# pcb_v3.net
KiCad netlist of a schematic drawn in EAGLE
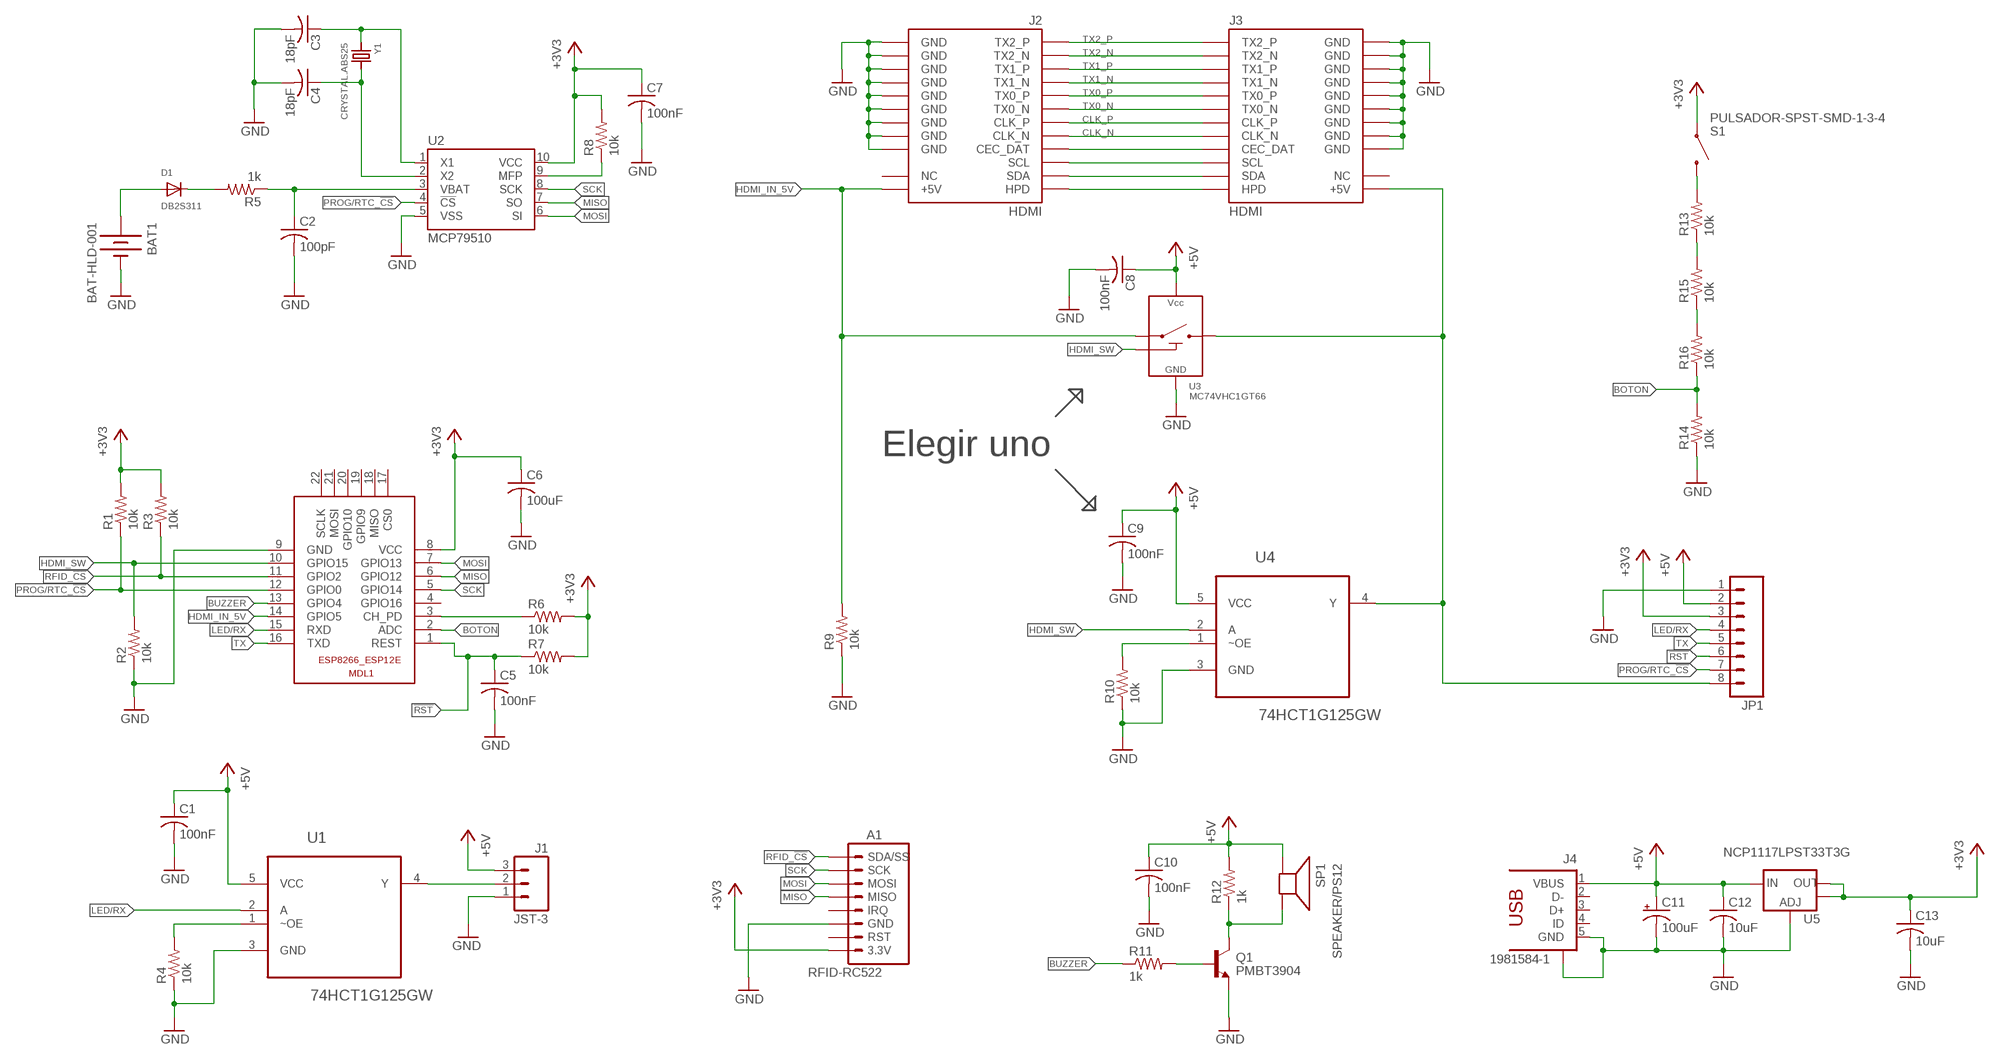
[diagram p0: schematic, sheet 1]

(export (version "E")
  (design (tool "Eeschema 10.0.6"))
  (components
    (comp (ref "A1")
      (value "RFID-RC522")
      (footprint "eagle-import:RFID-RC522")
      (libsource (lib "eagle-import") (part "RFID-RC522"))
    )
    (comp (ref "BAT1")
      (value "BAT-HLD-001")
      (footprint "eagle-import:BATTCON_20MM")
      (libsource (lib "eagle-import") (part "LINX-BAT-HLD-00120SMD"))
    )
    (comp (ref "C1")
      (value "100nF")
      (footprint "eagle-import:C0805")
      (libsource (lib "eagle-import") (part "C-USC0805"))
    )
    (comp (ref "C2")
      (value "100pF")
      (footprint "eagle-import:C0805")
      (libsource (lib "eagle-import") (part "C-USC0805"))
    )
    (comp (ref "C3")
      (value "18pF")
      (footprint "eagle-import:C0805")
      (libsource (lib "eagle-import") (part "C-USC0805"))
    )
    (comp (ref "C4")
      (value "18pF")
      (footprint "eagle-import:C0805")
      (libsource (lib "eagle-import") (part "C-USC0805"))
    )
    (comp (ref "C5")
      (value "100nF")
      (footprint "eagle-import:C0805")
      (libsource (lib "eagle-import") (part "C-USC0805"))
    )
    (comp (ref "C6")
      (value "100uF")
      (footprint "eagle-import:C1206")
      (libsource (lib "eagle-import") (part "C-USC1206"))
    )
    (comp (ref "C7")
      (value "100nF")
      (footprint "eagle-import:C0805")
      (libsource (lib "eagle-import") (part "C-USC0805"))
    )
    (comp (ref "C8")
      (value "100nF")
      (footprint "eagle-import:C0805")
      (libsource (lib "eagle-import") (part "C-USC0805"))
    )
    (comp (ref "C9")
      (value "100nF")
      (footprint "eagle-import:C0805")
      (libsource (lib "eagle-import") (part "C-USC0805"))
    )
    (comp (ref "C10")
      (value "100nF")
      (footprint "eagle-import:C0805")
      (libsource (lib "eagle-import") (part "C-USC0805"))
    )
    (comp (ref "C11")
      (value "100uF")
      (footprint "eagle-import:UD-6,3X5,8_NICHICON_LPADS")
      (libsource (lib "eagle-import") (part "CPOL-US"))
    )
    (comp (ref "C12")
      (value "10uF")
      (footprint "eagle-import:C0805")
      (libsource (lib "eagle-import") (part "C-USC0805"))
    )
    (comp (ref "C13")
      (value "10uF")
      (footprint "eagle-import:C0805")
      (libsource (lib "eagle-import") (part "C-USC0805"))
    )
    (comp (ref "D1")
      (value "DB2S311")
      (footprint "eagle-import:SOD-523")
      (libsource (lib "eagle-import") (part "DIODESOD-523"))
    )
    (comp (ref "J1")
      (value "JST-3")
      (footprint "eagle-import:B3B-PH-SM4-TB")
      (libsource (lib "eagle-import") (part "JST-3"))
    )
    (comp (ref "J2")
      (value "HDMI")
      (footprint "eagle-import:0471511071")
      (libsource (lib "eagle-import") (part "HDMI"))
    )
    (comp (ref "J3")
      (value "HDMI")
      (footprint "eagle-import:0471511071")
      (libsource (lib "eagle-import") (part "HDMI"))
    )
    (comp (ref "J4")
      (value "1981584-1")
      (footprint "eagle-import:1981584-1")
      (libsource (lib "eagle-import") (part "1981584-1"))
    )
    (comp (ref "JP1")
      (value "M081X08")
      (footprint "eagle-import:1X08")
      (libsource (lib "eagle-import") (part "M081X08"))
    )
    (comp (ref "MDL1")
      (value "ESP8266-12EESP8266-ESP12E")
      (footprint "eagle-import:ESP8266-ESP12E")
      (libsource (lib "eagle-import") (part "ESP8266-12EESP8266-ESP12E"))
    )
    (comp (ref "Q1")
      (value "PMBT3904")
      (footprint "eagle-import:SOT-23-3")
      (libsource (lib "eagle-import") (part "PMBT3904"))
    )
    (comp (ref "R1")
      (value "10k")
      (footprint "eagle-import:R0805")
      (libsource (lib "eagle-import") (part "R-US_R0805"))
    )
    (comp (ref "R2")
      (value "10k")
      (footprint "eagle-import:R0805")
      (libsource (lib "eagle-import") (part "R-US_R0805"))
    )
    (comp (ref "R3")
      (value "10k")
      (footprint "eagle-import:R0805")
      (libsource (lib "eagle-import") (part "R-US_R0805"))
    )
    (comp (ref "R4")
      (value "10k")
      (footprint "eagle-import:R0805")
      (libsource (lib "eagle-import") (part "R-US_R0805"))
    )
    (comp (ref "R5")
      (value "1k")
      (footprint "eagle-import:R0805")
      (libsource (lib "eagle-import") (part "R-US_R0805"))
    )
    (comp (ref "R6")
      (value "10k")
      (footprint "eagle-import:R0805")
      (libsource (lib "eagle-import") (part "R-US_R0805"))
    )
    (comp (ref "R7")
      (value "10k")
      (footprint "eagle-import:R0805")
      (libsource (lib "eagle-import") (part "R-US_R0805"))
    )
    (comp (ref "R8")
      (value "10k")
      (footprint "eagle-import:R0805")
      (libsource (lib "eagle-import") (part "R-US_R0805"))
    )
    (comp (ref "R9")
      (value "10k")
      (footprint "eagle-import:R0805")
      (libsource (lib "eagle-import") (part "R-US_R0805"))
    )
    (comp (ref "R10")
      (value "10k")
      (footprint "eagle-import:R0805")
      (libsource (lib "eagle-import") (part "R-US_R0805"))
    )
    (comp (ref "R11")
      (value "1k")
      (footprint "eagle-import:R0805")
      (libsource (lib "eagle-import") (part "R-US_R0805"))
    )
    (comp (ref "R12")
      (value "1k")
      (footprint "eagle-import:R0805")
      (libsource (lib "eagle-import") (part "R-US_R0805"))
    )
    (comp (ref "R13")
      (value "10k")
      (footprint "eagle-import:R0805")
      (libsource (lib "eagle-import") (part "R-US_R0805"))
    )
    (comp (ref "R14")
      (value "10k")
      (footprint "eagle-import:R0805")
      (libsource (lib "eagle-import") (part "R-US_R0805"))
    )
    (comp (ref "R15")
      (value "10k")
      (footprint "eagle-import:R0805")
      (libsource (lib "eagle-import") (part "R-US_R0805"))
    )
    (comp (ref "R16")
      (value "10k")
      (footprint "eagle-import:R0805")
      (libsource (lib "eagle-import") (part "R-US_R0805"))
    )
    (comp (ref "S1")
      (value "PULSADOR-SPST-SMD-1-3-4")
      (footprint "eagle-import:PTS645SM43SMTR92")
      (libsource (lib "eagle-import") (part "PULSADOR-SPST-SMD-1-3-4"))
    )
    (comp (ref "SP1")
      (value "SPEAKER/PS12")
      (footprint "eagle-import:PS12")
      (libsource (lib "eagle-import") (part "SPEAKER/PS12"))
    )
    (comp (ref "U1")
      (value "74HCT1G125GW")
      (footprint "eagle-import:SOT65P210X110-5N")
      (libsource (lib "eagle-import") (part "74HCT1G125GW"))
    )
    (comp (ref "U2")
      (value "MCP79510")
      (footprint "eagle-import:MSOP10")
      (libsource (lib "eagle-import") (part "MCP79510"))
    )
    (comp (ref "U3")
      (value "MC74VHC1GT66")
      (footprint "eagle-import:TSOP-5")
      (libsource (lib "eagle-import") (part "MC74VHC1GT66"))
    )
    (comp (ref "U4")
      (value "74HCT1G125GW")
      (footprint "eagle-import:SOT65P210X110-5N")
      (libsource (lib "eagle-import") (part "74HCT1G125GW"))
    )
    (comp (ref "U5")
      (value "NCP1117LPST33T3G")
      (footprint "eagle-import:SOT223")
      (libsource (lib "eagle-import") (part "V_REG_LM1117SOT223"))
    )
    (comp (ref "Y1")
      (value "CRYSTAL.ABS25")
      (footprint "eagle-import:ABS25")
      (libsource (lib "eagle-import") (part "CRYSTAL.ABS25"))
    )
  )
  (nets
    (net (code "1") (name "+3V3") (class "Default")
      (node (ref "A1") (pin "3.3V") (pinfunction "3.3V_3.3V") (pintype "passive"))
      (node (ref "C13") (pin "1") (pinfunction "1_1") (pintype "passive"))
      (node (ref "C6") (pin "1") (pinfunction "1_1") (pintype "passive"))
      (node (ref "C7") (pin "1") (pinfunction "1_1") (pintype "passive"))
      (node (ref "JP1") (pin "3") (pinfunction "3_3") (pintype "passive"))
      (node (ref "MDL1") (pin "8") (pinfunction "VCC_8") (pintype "bidirectional"))
      (node (ref "R1") (pin "2") (pinfunction "2_2") (pintype "passive"))
      (node (ref "R3") (pin "2") (pinfunction "2_2") (pintype "passive"))
      (node (ref "R6") (pin "2") (pinfunction "2_2") (pintype "passive"))
      (node (ref "R7") (pin "2") (pinfunction "2_2") (pintype "passive"))
      (node (ref "R8") (pin "2") (pinfunction "2_2") (pintype "passive"))
      (node (ref "S1") (pin "P$1") (pinfunction "P$1_P$1") (pintype "passive"))
      (node (ref "U2") (pin "10") (pinfunction "VCC_10") (pintype "bidirectional"))
      (node (ref "U5") (pin "2") (pinfunction "OUT_2") (pintype "output"))
      (node (ref "U5") (pin "4") (pinfunction "OUT_4") (pintype "output"))
    )
    (net (code "2") (name "+5V") (class "Default")
      (node (ref "C1") (pin "1") (pinfunction "1_1") (pintype "passive"))
      (node (ref "C10") (pin "1") (pinfunction "1_1") (pintype "passive"))
      (node (ref "C11") (pin "+") (pinfunction "+_+") (pintype "passive"))
      (node (ref "C12") (pin "1") (pinfunction "1_1") (pintype "passive"))
      (node (ref "C8") (pin "1") (pinfunction "1_1") (pintype "passive"))
      (node (ref "C9") (pin "1") (pinfunction "1_1") (pintype "passive"))
      (node (ref "J1") (pin "3") (pinfunction "3_3") (pintype "passive"))
      (node (ref "J4") (pin "1") (pinfunction "VBUS_1") (pintype "passive"))
      (node (ref "JP1") (pin "2") (pinfunction "2_2") (pintype "passive"))
      (node (ref "R12") (pin "2") (pinfunction "2_2") (pintype "passive"))
      (node (ref "SP1") (pin "P$1") (pinfunction "+_P$1") (pintype "passive"))
      (node (ref "U1") (pin "5") (pinfunction "VCC_5") (pintype "power_in"))
      (node (ref "U3") (pin "5") (pinfunction "P$5_5") (pintype "bidirectional"))
      (node (ref "U4") (pin "5") (pinfunction "VCC_5") (pintype "power_in"))
      (node (ref "U5") (pin "3") (pinfunction "IN_3") (pintype "input"))
    )
    (net (code "3") (name "/CLK_N") (class "Default")
      (node (ref "J2") (pin "P$12") (pinfunction "CLK_N_P$12") (pintype "bidirectional"))
      (node (ref "J3") (pin "P$12") (pinfunction "CLK_N_P$12") (pintype "bidirectional"))
    )
    (net (code "4") (name "/CLK_P") (class "Default")
      (node (ref "J2") (pin "P$10") (pinfunction "CLK_P_P$10") (pintype "bidirectional"))
      (node (ref "J3") (pin "P$10") (pinfunction "CLK_P_P$10") (pintype "bidirectional"))
    )
    (net (code "5") (name "/PROG{slash}RTC_~{CS}") (class "Default")
      (node (ref "JP1") (pin "7") (pinfunction "7_7") (pintype "passive"))
      (node (ref "MDL1") (pin "12") (pinfunction "GPIO0_12") (pintype "bidirectional"))
      (node (ref "R1") (pin "1") (pinfunction "1_1") (pintype "passive"))
      (node (ref "U2") (pin "4") (pinfunction "~{CS}_4") (pintype "bidirectional"))
    )
    (net (code "6") (name "/RFID_~{CS}") (class "Default")
      (node (ref "A1") (pin "SDA") (pinfunction "SDA/SS_SDA") (pintype "passive"))
      (node (ref "MDL1") (pin "11") (pinfunction "GPIO2_11") (pintype "bidirectional"))
      (node (ref "R3") (pin "1") (pinfunction "1_1") (pintype "passive"))
    )
    (net (code "7") (name "/TX0_N") (class "Default")
      (node (ref "J2") (pin "P$9") (pinfunction "TX0_N_P$9") (pintype "bidirectional"))
      (node (ref "J3") (pin "P$9") (pinfunction "TX0_N_P$9") (pintype "bidirectional"))
    )
    (net (code "8") (name "/TX0_P") (class "Default")
      (node (ref "J2") (pin "P$7") (pinfunction "TX0_P_P$7") (pintype "bidirectional"))
      (node (ref "J3") (pin "P$7") (pinfunction "TX0_P_P$7") (pintype "bidirectional"))
    )
    (net (code "9") (name "/TX1_N") (class "Default")
      (node (ref "J2") (pin "P$6") (pinfunction "TX1_N_P$6") (pintype "bidirectional"))
      (node (ref "J3") (pin "P$6") (pinfunction "TX1_N_P$6") (pintype "bidirectional"))
    )
    (net (code "10") (name "/TX1_P") (class "Default")
      (node (ref "J2") (pin "P$4") (pinfunction "TX1_P_P$4") (pintype "bidirectional"))
      (node (ref "J3") (pin "P$4") (pinfunction "TX1_P_P$4") (pintype "bidirectional"))
    )
    (net (code "11") (name "/TX2_N") (class "Default")
      (node (ref "J2") (pin "P$3") (pinfunction "TX2_N_P$3") (pintype "bidirectional"))
      (node (ref "J3") (pin "P$3") (pinfunction "TX2_N_P$3") (pintype "bidirectional"))
    )
    (net (code "12") (name "/TX2_P") (class "Default")
      (node (ref "J2") (pin "P$1") (pinfunction "TX2_P_P$1") (pintype "bidirectional"))
      (node (ref "J3") (pin "P$1") (pinfunction "TX2_P_P$1") (pintype "bidirectional"))
    )
    (net (code "13") (name "/~{RST}") (class "Default")
      (node (ref "C5") (pin "1") (pinfunction "1_1") (pintype "passive"))
      (node (ref "JP1") (pin "6") (pinfunction "6_6") (pintype "passive"))
      (node (ref "MDL1") (pin "1") (pinfunction "REST_1") (pintype "bidirectional"))
      (node (ref "R7") (pin "1") (pinfunction "1_1") (pintype "passive"))
    )
    (net (code "14") (name "BOTON") (class "Default")
      (node (ref "MDL1") (pin "2") (pinfunction "ADC_2") (pintype "bidirectional"))
      (node (ref "R14") (pin "2") (pinfunction "2_2") (pintype "passive"))
      (node (ref "R16") (pin "1") (pinfunction "1_1") (pintype "passive"))
    )
    (net (code "15") (name "BUZZER") (class "Default")
      (node (ref "MDL1") (pin "13") (pinfunction "GPIO4_13") (pintype "bidirectional"))
      (node (ref "R11") (pin "1") (pinfunction "1_1") (pintype "passive"))
    )
    (net (code "16") (name "GND") (class "Default")
      (node (ref "A1") (pin "GND") (pinfunction "GND_GND") (pintype "passive"))
      (node (ref "BAT1") (pin "2") (pinfunction "-_2") (pintype "power_in"))
      (node (ref "C1") (pin "2") (pinfunction "2_2") (pintype "passive"))
      (node (ref "C10") (pin "2") (pinfunction "2_2") (pintype "passive"))
      (node (ref "C11") (pin "-") (pinfunction "-_-") (pintype "passive"))
      (node (ref "C12") (pin "2") (pinfunction "2_2") (pintype "passive"))
      (node (ref "C13") (pin "2") (pinfunction "2_2") (pintype "passive"))
      (node (ref "C2") (pin "2") (pinfunction "2_2") (pintype "passive"))
      (node (ref "C3") (pin "2") (pinfunction "2_2") (pintype "passive"))
      (node (ref "C4") (pin "2") (pinfunction "2_2") (pintype "passive"))
      (node (ref "C5") (pin "2") (pinfunction "2_2") (pintype "passive"))
      (node (ref "C6") (pin "2") (pinfunction "2_2") (pintype "passive"))
      (node (ref "C7") (pin "2") (pinfunction "2_2") (pintype "passive"))
      (node (ref "C8") (pin "2") (pinfunction "2_2") (pintype "passive"))
      (node (ref "C9") (pin "2") (pinfunction "2_2") (pintype "passive"))
      (node (ref "J1") (pin "1") (pinfunction "1_1") (pintype "passive"))
      (node (ref "J2") (pin "P$11") (pinfunction "GND_P$11") (pintype "bidirectional"))
      (node (ref "J2") (pin "P$17") (pinfunction "GND_P$17") (pintype "bidirectional"))
      (node (ref "J2") (pin "P$2") (pinfunction "GND_P$2") (pintype "bidirectional"))
      (node (ref "J2") (pin "P$20") (pinfunction "GND_P$20") (pintype "bidirectional"))
      (node (ref "J2") (pin "P$21") (pinfunction "GND_P$21") (pintype "bidirectional"))
      (node (ref "J2") (pin "P$22") (pinfunction "GND_P$22") (pintype "bidirectional"))
      (node (ref "J2") (pin "P$23") (pinfunction "GND_P$23") (pintype "bidirectional"))
      (node (ref "J2") (pin "P$5") (pinfunction "GND_P$5") (pintype "bidirectional"))
      (node (ref "J2") (pin "P$8") (pinfunction "GND_P$8") (pintype "bidirectional"))
      (node (ref "J3") (pin "P$11") (pinfunction "GND_P$11") (pintype "bidirectional"))
      (node (ref "J3") (pin "P$17") (pinfunction "GND_P$17") (pintype "bidirectional"))
      (node (ref "J3") (pin "P$2") (pinfunction "GND_P$2") (pintype "bidirectional"))
      (node (ref "J3") (pin "P$20") (pinfunction "GND_P$20") (pintype "bidirectional"))
      (node (ref "J3") (pin "P$21") (pinfunction "GND_P$21") (pintype "bidirectional"))
      (node (ref "J3") (pin "P$22") (pinfunction "GND_P$22") (pintype "bidirectional"))
      (node (ref "J3") (pin "P$23") (pinfunction "GND_P$23") (pintype "bidirectional"))
      (node (ref "J3") (pin "P$5") (pinfunction "GND_P$5") (pintype "bidirectional"))
      (node (ref "J3") (pin "P$8") (pinfunction "GND_P$8") (pintype "bidirectional"))
      (node (ref "J4") (pin "5") (pinfunction "GND_5") (pintype "passive"))
      (node (ref "J4") (pin "S1") (pinfunction "S1_S1") (pintype "passive"))
      (node (ref "J4") (pin "S2") (pinfunction "S2_S2") (pintype "passive"))
      (node (ref "J4") (pin "S3") (pinfunction "S3_S3") (pintype "passive"))
      (node (ref "J4") (pin "S4") (pinfunction "S4_S4") (pintype "passive"))
      (node (ref "JP1") (pin "1") (pinfunction "1_1") (pintype "passive"))
      (node (ref "MDL1") (pin "9") (pinfunction "GND_9") (pintype "bidirectional"))
      (node (ref "Q1") (pin "2") (pinfunction "E_2") (pintype "passive"))
      (node (ref "R10") (pin "1") (pinfunction "1_1") (pintype "passive"))
      (node (ref "R14") (pin "1") (pinfunction "1_1") (pintype "passive"))
      (node (ref "R2") (pin "1") (pinfunction "1_1") (pintype "passive"))
      (node (ref "R4") (pin "1") (pinfunction "1_1") (pintype "passive"))
      (node (ref "R9") (pin "1") (pinfunction "1_1") (pintype "passive"))
      (node (ref "U1") (pin "3") (pinfunction "GND_3") (pintype "passive"))
      (node (ref "U2") (pin "5") (pinfunction "VSS_5") (pintype "bidirectional"))
      (node (ref "U3") (pin "3") (pinfunction "P$3_3") (pintype "bidirectional"))
      (node (ref "U4") (pin "3") (pinfunction "GND_3") (pintype "passive"))
      (node (ref "U5") (pin "1") (pinfunction "ADJ_1") (pintype "input"))
    )
    (net (code "17") (name "HDMI_IN_5V") (class "Default")
      (node (ref "J2") (pin "P$18") (pinfunction "+5V_P$18") (pintype "bidirectional"))
      (node (ref "MDL1") (pin "14") (pinfunction "GPIO5_14") (pintype "bidirectional"))
      (node (ref "R9") (pin "2") (pinfunction "2_2") (pintype "passive"))
      (node (ref "U3") (pin "1") (pinfunction "P$1_1") (pintype "bidirectional"))
    )
    (net (code "18") (name "HDMI_SW") (class "Default")
      (node (ref "MDL1") (pin "10") (pinfunction "GPIO15_10") (pintype "bidirectional"))
      (node (ref "R2") (pin "2") (pinfunction "2_2") (pintype "passive"))
      (node (ref "U3") (pin "4") (pinfunction "P$4_4") (pintype "bidirectional"))
      (node (ref "U4") (pin "2") (pinfunction "A_2") (pintype "input"))
    )
    (net (code "19") (name "LED{slash}RX") (class "Default")
      (node (ref "JP1") (pin "4") (pinfunction "4_4") (pintype "passive"))
      (node (ref "MDL1") (pin "15") (pinfunction "RXD_15") (pintype "bidirectional"))
      (node (ref "U1") (pin "2") (pinfunction "A_2") (pintype "input"))
    )
    (net (code "20") (name "MISO") (class "Default")
      (node (ref "A1") (pin "MISO") (pinfunction "MISO_MISO") (pintype "passive"))
      (node (ref "MDL1") (pin "6") (pinfunction "GPIO12_6") (pintype "bidirectional"))
      (node (ref "U2") (pin "7") (pinfunction "SO_7") (pintype "bidirectional"))
    )
    (net (code "21") (name "MOSI") (class "Default")
      (node (ref "A1") (pin "MOSI") (pinfunction "MOSI_MOSI") (pintype "passive"))
      (node (ref "MDL1") (pin "7") (pinfunction "GPIO13_7") (pintype "bidirectional"))
      (node (ref "U2") (pin "6") (pinfunction "SI_6") (pintype "bidirectional"))
    )
    (net (code "22") (name "Net-(BAT1-+)") (class "Default")
      (node (ref "BAT1") (pin "1") (pinfunction "+_1") (pintype "power_in"))
      (node (ref "D1") (pin "A") (pinfunction "A_A") (pintype "passive"))
    )
    (net (code "23") (name "Net-(D1-C)") (class "Default")
      (node (ref "D1") (pin "K") (pinfunction "C_K") (pintype "passive"))
      (node (ref "R5") (pin "2") (pinfunction "2_2") (pintype "passive"))
    )
    (net (code "24") (name "Net-(J2-CEC_DAT)") (class "Default")
      (node (ref "J2") (pin "P$13") (pinfunction "CEC_DAT_P$13") (pintype "bidirectional"))
      (node (ref "J3") (pin "P$13") (pinfunction "CEC_DAT_P$13") (pintype "bidirectional"))
    )
    (net (code "25") (name "Net-(J2-HPD)") (class "Default")
      (node (ref "J2") (pin "P$19") (pinfunction "HPD_P$19") (pintype "bidirectional"))
      (node (ref "J3") (pin "P$19") (pinfunction "HPD_P$19") (pintype "bidirectional"))
    )
    (net (code "26") (name "Net-(J2-SCL)") (class "Default")
      (node (ref "J2") (pin "P$15") (pinfunction "SCL_P$15") (pintype "bidirectional"))
      (node (ref "J3") (pin "P$15") (pinfunction "SCL_P$15") (pintype "bidirectional"))
    )
    (net (code "27") (name "Net-(J2-SDA)") (class "Default")
      (node (ref "J2") (pin "P$16") (pinfunction "SDA_P$16") (pintype "bidirectional"))
      (node (ref "J3") (pin "P$16") (pinfunction "SDA_P$16") (pintype "bidirectional"))
    )
    (net (code "28") (name "Net-(J3-+5V)") (class "Default")
      (node (ref "J3") (pin "P$18") (pinfunction "+5V_P$18") (pintype "bidirectional"))
      (node (ref "JP1") (pin "8") (pinfunction "8_8") (pintype "passive"))
      (node (ref "U3") (pin "2") (pinfunction "P$2_2") (pintype "bidirectional"))
      (node (ref "U4") (pin "4") (pinfunction "Y_4") (pintype "output"))
    )
    (net (code "29") (name "Net-(MDL1-CH_PD)") (class "Default")
      (node (ref "MDL1") (pin "3") (pinfunction "CH_PD_3") (pintype "bidirectional"))
      (node (ref "R6") (pin "1") (pinfunction "1_1") (pintype "passive"))
    )
    (net (code "30") (name "Net-(Q1-B)") (class "Default")
      (node (ref "Q1") (pin "1") (pinfunction "B_1") (pintype "passive"))
      (node (ref "R11") (pin "2") (pinfunction "2_2") (pintype "passive"))
    )
    (net (code "31") (name "Net-(Q1-C)") (class "Default")
      (node (ref "Q1") (pin "3") (pinfunction "C_3") (pintype "passive"))
      (node (ref "R12") (pin "1") (pinfunction "1_1") (pintype "passive"))
      (node (ref "SP1") (pin "P$2") (pinfunction "-_P$2") (pintype "passive"))
    )
    (net (code "32") (name "Net-(R13-Pad1)") (class "Default")
      (node (ref "R13") (pin "1") (pinfunction "1_1") (pintype "passive"))
      (node (ref "R15") (pin "2") (pinfunction "2_2") (pintype "passive"))
    )
    (net (code "33") (name "Net-(R13-Pad2)") (class "Default")
      (node (ref "R13") (pin "2") (pinfunction "2_2") (pintype "passive"))
      (node (ref "S1") (pin "P$3") (pinfunction "P$2_P$3") (pintype "passive"))
      (node (ref "S1") (pin "P$4") (pinfunction "P$2_P$4") (pintype "passive"))
    )
    (net (code "34") (name "Net-(R15-Pad1)") (class "Default")
      (node (ref "R15") (pin "1") (pinfunction "1_1") (pintype "passive"))
      (node (ref "R16") (pin "2") (pinfunction "2_2") (pintype "passive"))
    )
    (net (code "35") (name "Net-(U1-Y)") (class "Default")
      (node (ref "J1") (pin "2") (pinfunction "2_2") (pintype "passive"))
      (node (ref "U1") (pin "4") (pinfunction "Y_4") (pintype "output"))
    )
    (net (code "36") (name "Net-(U1-~{OE})") (class "Default")
      (node (ref "R4") (pin "2") (pinfunction "2_2") (pintype "passive"))
      (node (ref "U1") (pin "1") (pinfunction "~{OE}_1") (pintype "input"))
    )
    (net (code "37") (name "Net-(U2-MFP)") (class "Default")
      (node (ref "R8") (pin "1") (pinfunction "1_1") (pintype "passive"))
      (node (ref "U2") (pin "9") (pinfunction "MFP_9") (pintype "bidirectional"))
    )
    (net (code "38") (name "Net-(U2-VBAT)") (class "Default")
      (node (ref "C2") (pin "1") (pinfunction "1_1") (pintype "passive"))
      (node (ref "R5") (pin "1") (pinfunction "1_1") (pintype "passive"))
      (node (ref "U2") (pin "3") (pinfunction "VBAT_3") (pintype "bidirectional"))
    )
    (net (code "39") (name "Net-(U2-X1)") (class "Default")
      (node (ref "C3") (pin "1") (pinfunction "1_1") (pintype "passive"))
      (node (ref "U2") (pin "1") (pinfunction "X1_1") (pintype "bidirectional"))
      (node (ref "Y1") (pin "1") (pinfunction "1_1") (pintype "passive"))
    )
    (net (code "40") (name "Net-(U2-X2)") (class "Default")
      (node (ref "C4") (pin "1") (pinfunction "1_1") (pintype "passive"))
      (node (ref "U2") (pin "2") (pinfunction "X2_2") (pintype "bidirectional"))
      (node (ref "Y1") (pin "4") (pinfunction "2_4") (pintype "passive"))
    )
    (net (code "41") (name "Net-(U4-~{OE})") (class "Default")
      (node (ref "R10") (pin "2") (pinfunction "2_2") (pintype "passive"))
      (node (ref "U4") (pin "1") (pinfunction "~{OE}_1") (pintype "input"))
    )
    (net (code "42") (name "SCK") (class "Default")
      (node (ref "A1") (pin "SCK") (pinfunction "SCK_SCK") (pintype "passive"))
      (node (ref "MDL1") (pin "5") (pinfunction "GPIO14_5") (pintype "bidirectional"))
      (node (ref "U2") (pin "8") (pinfunction "SCK_8") (pintype "bidirectional"))
    )
    (net (code "43") (name "TX") (class "Default")
      (node (ref "JP1") (pin "5") (pinfunction "5_5") (pintype "passive"))
      (node (ref "MDL1") (pin "16") (pinfunction "TXD_16") (pintype "bidirectional"))
    )
    (net (code "44") (name "unconnected-(A1-PadIRQ)") (class "Default")
      (node (ref "A1") (pin "IRQ") (pinfunction "IRQ_IRQ") (pintype "passive"))
    )
    (net (code "45") (name "unconnected-(A1-PadRST)") (class "Default")
      (node (ref "A1") (pin "RST") (pinfunction "RST_RST") (pintype "passive"))
    )
    (net (code "46") (name "unconnected-(J2-NC-PadP$14)") (class "Default")
      (node (ref "J2") (pin "P$14") (pinfunction "NC_P$14") (pintype "bidirectional"))
    )
    (net (code "47") (name "unconnected-(J3-NC-PadP$14)") (class "Default")
      (node (ref "J3") (pin "P$14") (pinfunction "NC_P$14") (pintype "bidirectional"))
    )
    (net (code "48") (name "unconnected-(J4-D+-Pad3)") (class "Default")
      (node (ref "J4") (pin "3") (pinfunction "D+_3") (pintype "passive"))
    )
    (net (code "49") (name "unconnected-(J4-D--Pad2)") (class "Default")
      (node (ref "J4") (pin "2") (pinfunction "D-_2") (pintype "passive"))
    )
    (net (code "50") (name "unconnected-(J4-ID-Pad4)") (class "Default")
      (node (ref "J4") (pin "4") (pinfunction "ID_4") (pintype "passive"))
    )
    (net (code "51") (name "unconnected-(MDL1-CS0-Pad17)") (class "Default")
      (node (ref "MDL1") (pin "17") (pinfunction "CS0_17") (pintype "bidirectional"))
    )
    (net (code "52") (name "unconnected-(MDL1-GPIO9-Pad19)") (class "Default")
      (node (ref "MDL1") (pin "19") (pinfunction "GPIO9_19") (pintype "bidirectional"))
    )
    (net (code "53") (name "unconnected-(MDL1-GPIO10-Pad20)") (class "Default")
      (node (ref "MDL1") (pin "20") (pinfunction "GPIO10_20") (pintype "bidirectional"))
    )
    (net (code "54") (name "unconnected-(MDL1-GPIO16-Pad4)") (class "Default")
      (node (ref "MDL1") (pin "4") (pinfunction "GPIO16_4") (pintype "bidirectional"))
    )
    (net (code "55") (name "unconnected-(MDL1-MISO-Pad18)") (class "Default")
      (node (ref "MDL1") (pin "18") (pinfunction "MISO_18") (pintype "bidirectional"))
    )
    (net (code "56") (name "unconnected-(MDL1-MOSI-Pad21)") (class "Default")
      (node (ref "MDL1") (pin "21") (pinfunction "MOSI_21") (pintype "bidirectional"))
    )
    (net (code "57") (name "unconnected-(MDL1-SCLK-Pad22)") (class "Default")
      (node (ref "MDL1") (pin "22") (pinfunction "SCLK_22") (pintype "bidirectional"))
    )
  )
)
